# INPUT_PROTECTION.net
KiCad netlist of a schematic drawn in Altium Designer
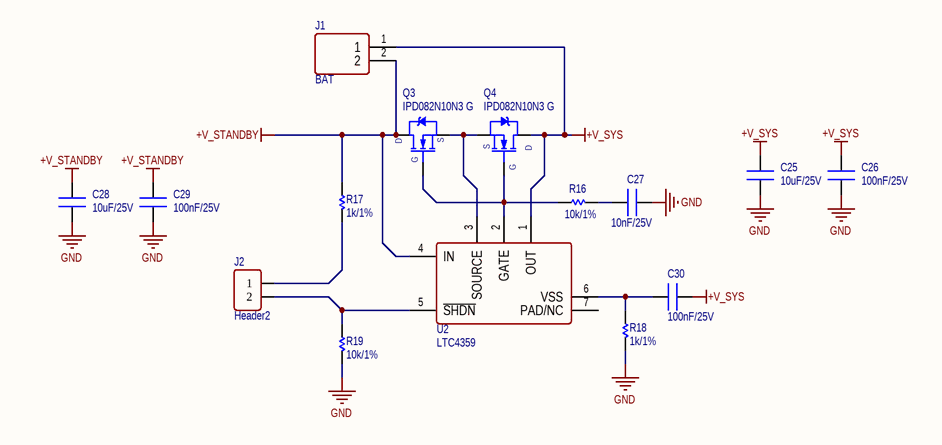
[diagram p0: INPUT_PROTECTION.SchDoc]

(export (version "E")
  (design (tool "Eeschema 10.0.6"))
  (components
    (comp (ref "C25")
      (value "10uF/25V")
      (footprint "CN-SMD-0603")
      (description "0603W106M250XD")
      (libsource (lib "Library") (part "CN"))
    )
    (comp (ref "C26")
      (value "100nF/25V")
      (footprint "CN-SMD-0603")
      (description "CL10B104KA8NNNC")
      (libsource (lib "Library") (part "CN"))
    )
    (comp (ref "C27")
      (value "10nF/25V")
      (footprint "CN-SMD-0603")
      (description "CL10B103KB8NNNC")
      (libsource (lib "Library") (part "CN"))
    )
    (comp (ref "C28")
      (value "10uF/25V")
      (footprint "CN-SMD-0603")
      (description "0603W106M250XD")
      (libsource (lib "Library") (part "CN"))
    )
    (comp (ref "C29")
      (value "100nF/25V")
      (footprint "CN-SMD-0603")
      (description "CL10B104KA8NNNC")
      (libsource (lib "Library") (part "CN"))
    )
    (comp (ref "C30")
      (value "100nF/25V")
      (footprint "CN-SMD-0603")
      (description "CL10B104KA8NNNC")
      (libsource (lib "Library") (part "CN"))
    )
    (comp (ref "J1")
      (value "BAT")
      (footprint "S2P-VH(LF)(SN)")
      (description "S2P-VH")
      (libsource (lib "Library") (part "KF2"))
    )
    (comp (ref "J2")
      (value "Header2")
      (footprint "XH2.54-2-DIP")
      (description "Connector 2")
      (fields
        (field (name "MANUFACTURER") "Würth Elektronik eiSos GmbH")
        (field (name "PARTNO") "613002143121")
        (field (name "CREATED BY") "Karrer Zheng")
      )
      (libsource (lib "Library") (part "Header2"))
    )
    (comp (ref "Q3")
      (value "IPD082N10N3 G")
      (footprint "TO252-123")
      (libsource (lib "Library") (part "FDD8870"))
    )
    (comp (ref "Q4")
      (value "IPD082N10N3 G")
      (footprint "TO252-123")
      (libsource (lib "Library") (part "FDD8870"))
    )
    (comp (ref "R16")
      (value "10k/1%")
      (footprint "RES-SMD-0603")
      (description "ERJ-3EKF1002V")
      (fields
        (field (name "MANUFACTURER") "Generic Components")
        (field (name "PUBLISHER") "Altium Hobart Technology Centre")
      )
      (libsource (lib "Library") (part "Res-SMD"))
    )
    (comp (ref "R17")
      (value "1k/1%")
      (footprint "RES-SMD-0603")
      (description "ERJ-3EKF1001V")
      (fields
        (field (name "MANUFACTURER") "Generic Components")
        (field (name "PUBLISHER") "Altium Hobart Technology Centre")
      )
      (libsource (lib "Library") (part "Res-SMD"))
    )
    (comp (ref "R18")
      (value "1k/1%")
      (footprint "RES-SMD-0603")
      (description "ERJ-3EKF1001V")
      (fields
        (field (name "MANUFACTURER") "Generic Components")
        (field (name "PUBLISHER") "Altium Hobart Technology Centre")
      )
      (libsource (lib "Library") (part "Res-SMD"))
    )
    (comp (ref "R19")
      (value "10k/1%")
      (footprint "RES-SMD-0603")
      (description "ERJ-3EKF1002V")
      (fields
        (field (name "MANUFACTURER") "Generic Components")
        (field (name "PUBLISHER") "Altium Hobart Technology Centre")
      )
      (libsource (lib "Library") (part "Res-SMD"))
    )
    (comp (ref "U2")
      (value "LTC4359")
      (footprint "VSSOP8")
      (description "Ideal Diode Controller with Reverse Input Protection")
      (libsource (lib "Library") (part "LTC4359"))
    )
  )
  (nets
    (net (code "1") (name "+V_STANDBY") (class "Default")
      (node (ref "C28") (pin "2") (pinfunction "2_2") (pintype "passive"))
      (node (ref "C29") (pin "2") (pinfunction "2_2") (pintype "passive"))
      (node (ref "J1") (pin "2") (pinfunction "2_2") (pintype "passive"))
      (node (ref "Q3") (pin "2") (pinfunction "D_2") (pintype "passive"))
      (node (ref "R17") (pin "1") (pinfunction "1_1") (pintype "passive"))
      (node (ref "U2") (pin "4") (pinfunction "IN_4") (pintype "passive"))
    )
    (net (code "2") (name "+V_SYS") (class "Default")
      (node (ref "C25") (pin "2") (pinfunction "2_2") (pintype "passive"))
      (node (ref "C26") (pin "2") (pinfunction "2_2") (pintype "passive"))
      (node (ref "C30") (pin "2") (pinfunction "2_2") (pintype "passive"))
      (node (ref "J1") (pin "1") (pinfunction "1_1") (pintype "passive"))
      (node (ref "Q4") (pin "2") (pinfunction "D_2") (pintype "passive"))
      (node (ref "U2") (pin "1") (pinfunction "OUT_1") (pintype "passive"))
    )
    (net (code "3") (name "GND") (class "Default")
      (node (ref "C25") (pin "1") (pinfunction "1_1") (pintype "passive"))
      (node (ref "C26") (pin "1") (pinfunction "1_1") (pintype "passive"))
      (node (ref "C27") (pin "1") (pinfunction "1_1") (pintype "passive"))
      (node (ref "C28") (pin "1") (pinfunction "1_1") (pintype "passive"))
      (node (ref "C29") (pin "1") (pinfunction "1_1") (pintype "passive"))
      (node (ref "R18") (pin "2") (pinfunction "2_2") (pintype "passive"))
      (node (ref "R19") (pin "2") (pinfunction "2_2") (pintype "passive"))
    )
    (net (code "4") (name "Net-(C27-Pad2)") (class "Default")
      (node (ref "C27") (pin "2") (pinfunction "2_2") (pintype "passive"))
      (node (ref "R16") (pin "2") (pinfunction "2_2") (pintype "passive"))
    )
    (net (code "5") (name "Net-(J2-Pad1)") (class "Default")
      (node (ref "J2") (pin "1") (pinfunction "1_1") (pintype "passive"))
      (node (ref "R17") (pin "2") (pinfunction "2_2") (pintype "passive"))
    )
    (net (code "6") (name "Net-(Q3-G)") (class "Default")
      (node (ref "Q3") (pin "1") (pinfunction "G_1") (pintype "passive"))
      (node (ref "Q4") (pin "1") (pinfunction "G_1") (pintype "passive"))
      (node (ref "R16") (pin "1") (pinfunction "1_1") (pintype "passive"))
      (node (ref "U2") (pin "2") (pinfunction "GATE_2") (pintype "passive"))
    )
    (net (code "7") (name "Net-(Q3-S)") (class "Default")
      (node (ref "Q3") (pin "3") (pinfunction "S_3") (pintype "passive"))
      (node (ref "Q4") (pin "3") (pinfunction "S_3") (pintype "passive"))
      (node (ref "U2") (pin "3") (pinfunction "SOURCE_3") (pintype "passive"))
    )
    (net (code "8") (name "Net-(U2-VSS)") (class "Default")
      (node (ref "C30") (pin "1") (pinfunction "1_1") (pintype "passive"))
      (node (ref "R18") (pin "1") (pinfunction "1_1") (pintype "passive"))
      (node (ref "U2") (pin "6") (pinfunction "VSS_6") (pintype "passive"))
    )
    (net (code "9") (name "Net-(U2-~{SHDN})") (class "Default")
      (node (ref "J2") (pin "2") (pinfunction "2_2") (pintype "passive"))
      (node (ref "R19") (pin "1") (pinfunction "1_1") (pintype "passive"))
      (node (ref "U2") (pin "5") (pinfunction "~{SHDN}_5") (pintype "passive"))
    )
    (net (code "10") (name "unconnected-(U2-PAD{slash}NC-Pad7)") (class "Default")
      (node (ref "U2") (pin "7") (pinfunction "PAD/NC_7") (pintype "passive"))
    )
  )
)
